# OSC.net
KiCad netlist of a schematic drawn in Altium Designer
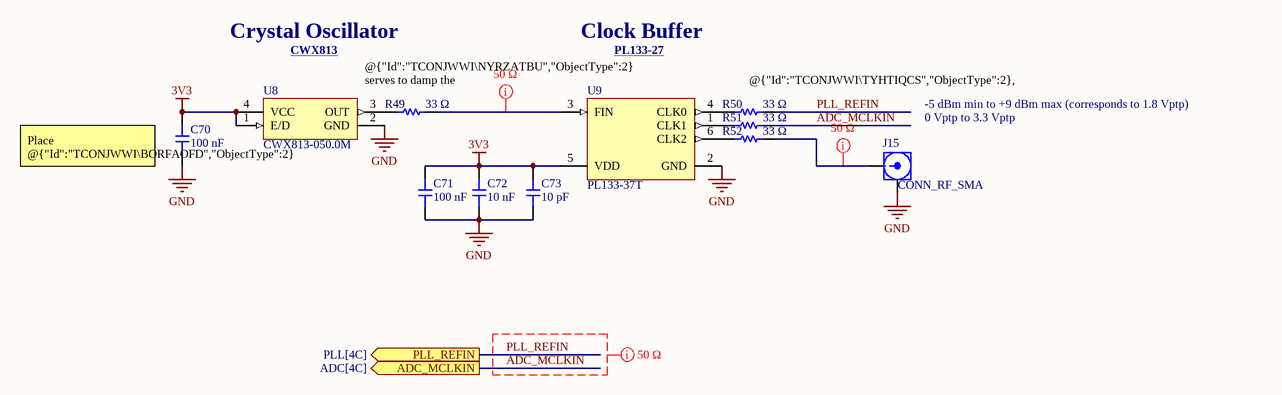
[diagram p0: OSC.SchDoc]

(export (version "E")
  (design (tool "Eeschema 10.0.6"))
  (components
    (comp (ref "C70")
      (value "100 nF")
      (footprint "CAP_0402")
      (description "25V 100nF X7R ±10% 0402 Multilayer Ceramic Capacitors MLCC - SMD/SMT ROHS")
      (fields
        (field (name "MANUFACTURER") "Samsung Electro-Mechanics")
        (field (name "MANUFACTURER PART NUMBER") "CL05B104KA5NNNC")
      )
      (libsource (lib "Titan") (part "CAP"))
    )
    (comp (ref "C71")
      (value "100 nF")
      (footprint "CAP_0402")
      (description "25V 100nF X7R ±10% 0402 Multilayer Ceramic Capacitors MLCC - SMD/SMT ROHS")
      (fields
        (field (name "MANUFACTURER") "Samsung Electro-Mechanics")
        (field (name "MANUFACTURER PART NUMBER") "CL05B104KA5NNNC")
      )
      (libsource (lib "Titan") (part "CAP"))
    )
    (comp (ref "C72")
      (value "10 nF")
      (footprint "CAP_0402")
      (description "Ceramic Capacitor, Ceramic, 50V, 10% +Tol, 10% -Tol, X7R, 15% TC, 0.01uF, Surface Mount, 0402")
      (fields
        (field (name "MANUFACTURER") "Yageo")
        (field (name "MANUFACTURER PART NUMBER") "CC0402KPX7R9BB103")
      )
      (libsource (lib "Titan") (part "CAP"))
    )
    (comp (ref "C73")
      (value "10 pF")
      (footprint "CAP_0402")
      (description "50V 10pF C0G ±5% 0402 Multilayer Ceramic Capacitors MLCC - SMD/SMT ROHS")
      (fields
        (field (name "MANUFACTURER") "Murata Electronics")
        (field (name "MANUFACTURER PART NUMBER") "GRM1555C1H100JA01D")
      )
      (libsource (lib "Titan") (part "CAP"))
    )
    (comp (ref "J15")
      (value "CONN_RF_SMA")
      (footprint "142-0701-801")
      (description "RF / Coaxial Connector, SMA Coaxial, Straight Jack, Solder, 50 ohm, Beryllium Copper")
      (fields
        (field (name "MANUFACTURER") "Cinch Connectivity Solutions Johnson")
        (field (name "MANUFACTURER PART NUMBER") "142-0701-801")
      )
      (libsource (lib "Titan") (part "CONN_RF_SMA"))
    )
    (comp (ref "R49")
      (value "33 Ω")
      (footprint "RES_0603")
      (description "100mW Thick Film Resistors 75V ±100ppm/℃ ±1% 33Ω 0603 Chip Resistor - Surface Mount ROHS")
      (fields
        (field (name "MANUFACTURER") "Yageo")
        (field (name "MANUFACTURER PART NUMBER") "RC0603FR-0733RL")
      )
      (libsource (lib "Titan") (part "RES"))
    )
    (comp (ref "R50")
      (value "33 Ω")
      (footprint "RES_0603")
      (description "100mW Thick Film Resistors 75V ±100ppm/℃ ±1% 33Ω 0603 Chip Resistor - Surface Mount ROHS")
      (fields
        (field (name "MANUFACTURER") "Yageo")
        (field (name "MANUFACTURER PART NUMBER") "RC0603FR-0733RL")
      )
      (libsource (lib "Titan") (part "RES"))
    )
    (comp (ref "R51")
      (value "33 Ω")
      (footprint "RES_0603")
      (description "100mW Thick Film Resistors 75V ±100ppm/℃ ±1% 33Ω 0603 Chip Resistor - Surface Mount ROHS")
      (fields
        (field (name "MANUFACTURER") "Yageo")
        (field (name "MANUFACTURER PART NUMBER") "RC0603FR-0733RL")
      )
      (libsource (lib "Titan") (part "RES"))
    )
    (comp (ref "R52")
      (value "33 Ω")
      (footprint "RES_0603")
      (description "100mW Thick Film Resistors 75V ±100ppm/℃ ±1% 33Ω 0603 Chip Resistor - Surface Mount ROHS")
      (fields
        (field (name "MANUFACTURER") "Yageo")
        (field (name "MANUFACTURER PART NUMBER") "RC0603FR-0733RL")
      )
      (libsource (lib "Titan") (part "RES"))
    )
    (comp (ref "U8")
      (value "CWX813-050.0M")
      (footprint "CWX8XX")
      (description "LVCMOS Output Clock Oscillator, 50MHz Nom")
      (fields (field (name "MANUFACTURER") "Connor-Winfield"))
      (libsource (lib "Titan") (part "CWX813-050.0M"))
    )
    (comp (ref "U9")
      (value "PL133-37T")
      (footprint "PL133-37T")
      (description "IC CLK BUFFER 1: 3 150MHZ SOT23-6 Clock Fanout Buffer (Distribution) IC 1: 3 150 MHz SOT-23-6")
      (fields
        (field (name "MANUFACTURER") "Microchip Technology")
        (field (name "MANUFACTURER PART NUMBER") "PL133-37TC-R")
      )
      (libsource (lib "Titan") (part "PL133-37T"))
    )
  )
  (nets
    (net (code "1") (name "/ADC_MCLKIN") (class "Default") (node (ref "R51") (pin "2") (pintype "passive")))
    (net (code "2") (name "/PLL_REFIN") (class "Default") (node (ref "R50") (pin "2") (pintype "passive")))
    (net (code "3") (name "3V3") (class "Default")
      (node (ref "C70") (pin "2") (pintype "passive"))
      (node (ref "C71") (pin "2") (pintype "passive"))
      (node (ref "C72") (pin "2") (pintype "passive"))
      (node (ref "C73") (pin "2") (pintype "passive"))
      (node (ref "U8") (pin "1") (pinfunction "E/D_1") (pintype "input"))
      (node (ref "U8") (pin "4") (pinfunction "VCC_4") (pintype "power_in"))
      (node (ref "U9") (pin "5") (pinfunction "VDD_5") (pintype "power_in"))
    )
    (net (code "4") (name "GND") (class "Default")
      (node (ref "C70") (pin "1") (pintype "passive"))
      (node (ref "C71") (pin "1") (pintype "passive"))
      (node (ref "C72") (pin "1") (pintype "passive"))
      (node (ref "C73") (pin "1") (pintype "passive"))
      (node (ref "J15") (pin "2") (pintype "passive"))
      (node (ref "U8") (pin "2") (pinfunction "GND_2") (pintype "power_in"))
      (node (ref "U9") (pin "2") (pinfunction "GND_2") (pintype "power_in"))
    )
    (net (code "5") (name "Net-(J15-Pad1)") (class "Default")
      (node (ref "J15") (pin "1") (pintype "passive"))
      (node (ref "R52") (pin "2") (pintype "passive"))
    )
    (net (code "6") (name "Net-(U8-OUT)") (class "Default")
      (node (ref "R49") (pin "1") (pintype "passive"))
      (node (ref "U8") (pin "3") (pinfunction "OUT_3") (pintype "output"))
    )
    (net (code "7") (name "Net-(U9-CLK0)") (class "Default")
      (node (ref "R50") (pin "1") (pintype "passive"))
      (node (ref "U9") (pin "4") (pinfunction "CLK0_4") (pintype "output"))
    )
    (net (code "8") (name "Net-(U9-CLK1)") (class "Default")
      (node (ref "R51") (pin "1") (pintype "passive"))
      (node (ref "U9") (pin "1") (pinfunction "CLK1_1") (pintype "output"))
    )
    (net (code "9") (name "Net-(U9-CLK2)") (class "Default")
      (node (ref "R52") (pin "1") (pintype "passive"))
      (node (ref "U9") (pin "6") (pinfunction "CLK2_6") (pintype "output"))
    )
    (net (code "10") (name "Net-(U9-FIN)") (class "Default")
      (node (ref "R49") (pin "2") (pintype "passive"))
      (node (ref "U9") (pin "3") (pinfunction "FIN_3") (pintype "input"))
    )
  )
)
